# ATtiny20_Study_-_SOIC14.net
KiCad netlist of a schematic drawn in EAGLE
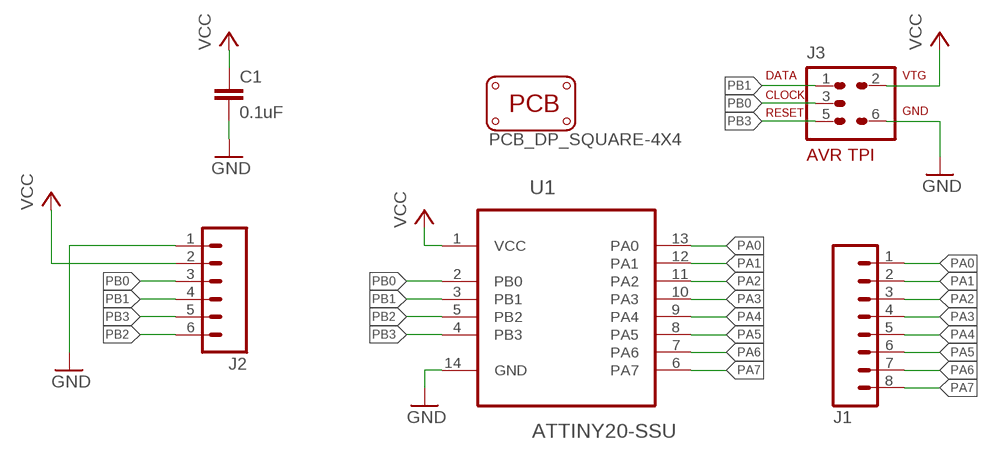
[diagram p0: schematic, sheet 1]

(export (version "E")
  (design (tool "Eeschema 10.0.6"))
  (components
    (comp (ref "C1")
      (value "0.1uF")
      (footprint "eagle-import:0805")
      (libsource (lib "eagle-import") (part "CAP0805"))
    )
    (comp (ref "J1")
      (value "M08NO_SILK_FEMALE_PTH")
      (footprint "eagle-import:1X08_NO_SILK")
      (libsource (lib "eagle-import") (part "M08NO_SILK_FEMALE_PTH"))
    )
    (comp (ref "J2")
      (value "M06NO_SILK_FEMALE_PTH")
      (footprint "eagle-import:1X06_NO_SILK")
      (libsource (lib "eagle-import") (part "M06NO_SILK_FEMALE_PTH"))
    )
    (comp (ref "J3")
      (value "AVR-TPIVERT")
      (footprint "eagle-import:AVR-ISP-6")
      (libsource (lib "eagle-import") (part "AVR-TPIVERT"))
    )
    (comp (ref "PCB1")
      (value "PCB_DP_SQUARE-4X4")
      (footprint "eagle-import:DP4040_V1")
      (libsource (lib "eagle-import") (part "PCB_DP_SQUARE-4X4"))
    )
    (comp (ref "U1")
      (value "ATTINY20-SSU")
      (footprint "eagle-import:14S1")
      (libsource (lib "eagle-import") (part "ATTINY20-SSU"))
    )
  )
  (nets
    (net (code "1") (name "GND") (class "Default")
      (node (ref "C1") (pin "2") (pinfunction "2_2") (pintype "passive"))
      (node (ref "J2") (pin "1") (pinfunction "1_1") (pintype "passive"))
      (node (ref "J3") (pin "6") (pinfunction "6_6") (pintype "passive"))
      (node (ref "U1") (pin "14") (pinfunction "GND_14") (pintype "passive"))
    )
    (net (code "2") (name "PA0") (class "Default")
      (node (ref "J1") (pin "1") (pinfunction "1_1") (pintype "passive"))
      (node (ref "U1") (pin "13") (pinfunction "PA0_13") (pintype "bidirectional"))
    )
    (net (code "3") (name "PA1") (class "Default")
      (node (ref "J1") (pin "2") (pinfunction "2_2") (pintype "passive"))
      (node (ref "U1") (pin "12") (pinfunction "PA1_12") (pintype "bidirectional"))
    )
    (net (code "4") (name "PA2") (class "Default")
      (node (ref "J1") (pin "3") (pinfunction "3_3") (pintype "passive"))
      (node (ref "U1") (pin "11") (pinfunction "PA2_11") (pintype "bidirectional"))
    )
    (net (code "5") (name "PA3") (class "Default")
      (node (ref "J1") (pin "4") (pinfunction "4_4") (pintype "passive"))
      (node (ref "U1") (pin "10") (pinfunction "PA3_10") (pintype "bidirectional"))
    )
    (net (code "6") (name "PA4") (class "Default")
      (node (ref "J1") (pin "5") (pinfunction "5_5") (pintype "passive"))
      (node (ref "U1") (pin "9") (pinfunction "PA4_9") (pintype "bidirectional"))
    )
    (net (code "7") (name "PA5") (class "Default")
      (node (ref "J1") (pin "6") (pinfunction "6_6") (pintype "passive"))
      (node (ref "U1") (pin "8") (pinfunction "PA5_8") (pintype "bidirectional"))
    )
    (net (code "8") (name "PA6") (class "Default")
      (node (ref "J1") (pin "7") (pinfunction "7_7") (pintype "passive"))
      (node (ref "U1") (pin "7") (pinfunction "PA6_7") (pintype "bidirectional"))
    )
    (net (code "9") (name "PA7") (class "Default")
      (node (ref "J1") (pin "8") (pinfunction "8_8") (pintype "passive"))
      (node (ref "U1") (pin "6") (pinfunction "PA7_6") (pintype "bidirectional"))
    )
    (net (code "10") (name "PB0") (class "Default")
      (node (ref "J2") (pin "3") (pinfunction "3_3") (pintype "passive"))
      (node (ref "J3") (pin "3") (pinfunction "3_3") (pintype "passive"))
      (node (ref "U1") (pin "2") (pinfunction "PB0_2") (pintype "bidirectional"))
    )
    (net (code "11") (name "PB1") (class "Default")
      (node (ref "J2") (pin "4") (pinfunction "4_4") (pintype "passive"))
      (node (ref "J3") (pin "1") (pinfunction "1_1") (pintype "passive"))
      (node (ref "U1") (pin "3") (pinfunction "PB1_3") (pintype "bidirectional"))
    )
    (net (code "12") (name "PB2") (class "Default")
      (node (ref "J2") (pin "6") (pinfunction "6_6") (pintype "passive"))
      (node (ref "U1") (pin "5") (pinfunction "PB2_5") (pintype "bidirectional"))
    )
    (net (code "13") (name "PB3") (class "Default")
      (node (ref "J2") (pin "5") (pinfunction "5_5") (pintype "passive"))
      (node (ref "J3") (pin "5") (pinfunction "5_5") (pintype "passive"))
      (node (ref "U1") (pin "4") (pinfunction "PB3_4") (pintype "bidirectional"))
    )
    (net (code "14") (name "VCC") (class "Default")
      (node (ref "C1") (pin "1") (pinfunction "1_1") (pintype "passive"))
      (node (ref "J2") (pin "2") (pinfunction "2_2") (pintype "passive"))
      (node (ref "J3") (pin "2") (pinfunction "2_2") (pintype "passive"))
      (node (ref "U1") (pin "1") (pinfunction "VCC_1") (pintype "power_in"))
    )
  )
)
